# pwm-sg3525a.net
KiCad netlist of a schematic drawn in Altium Designer
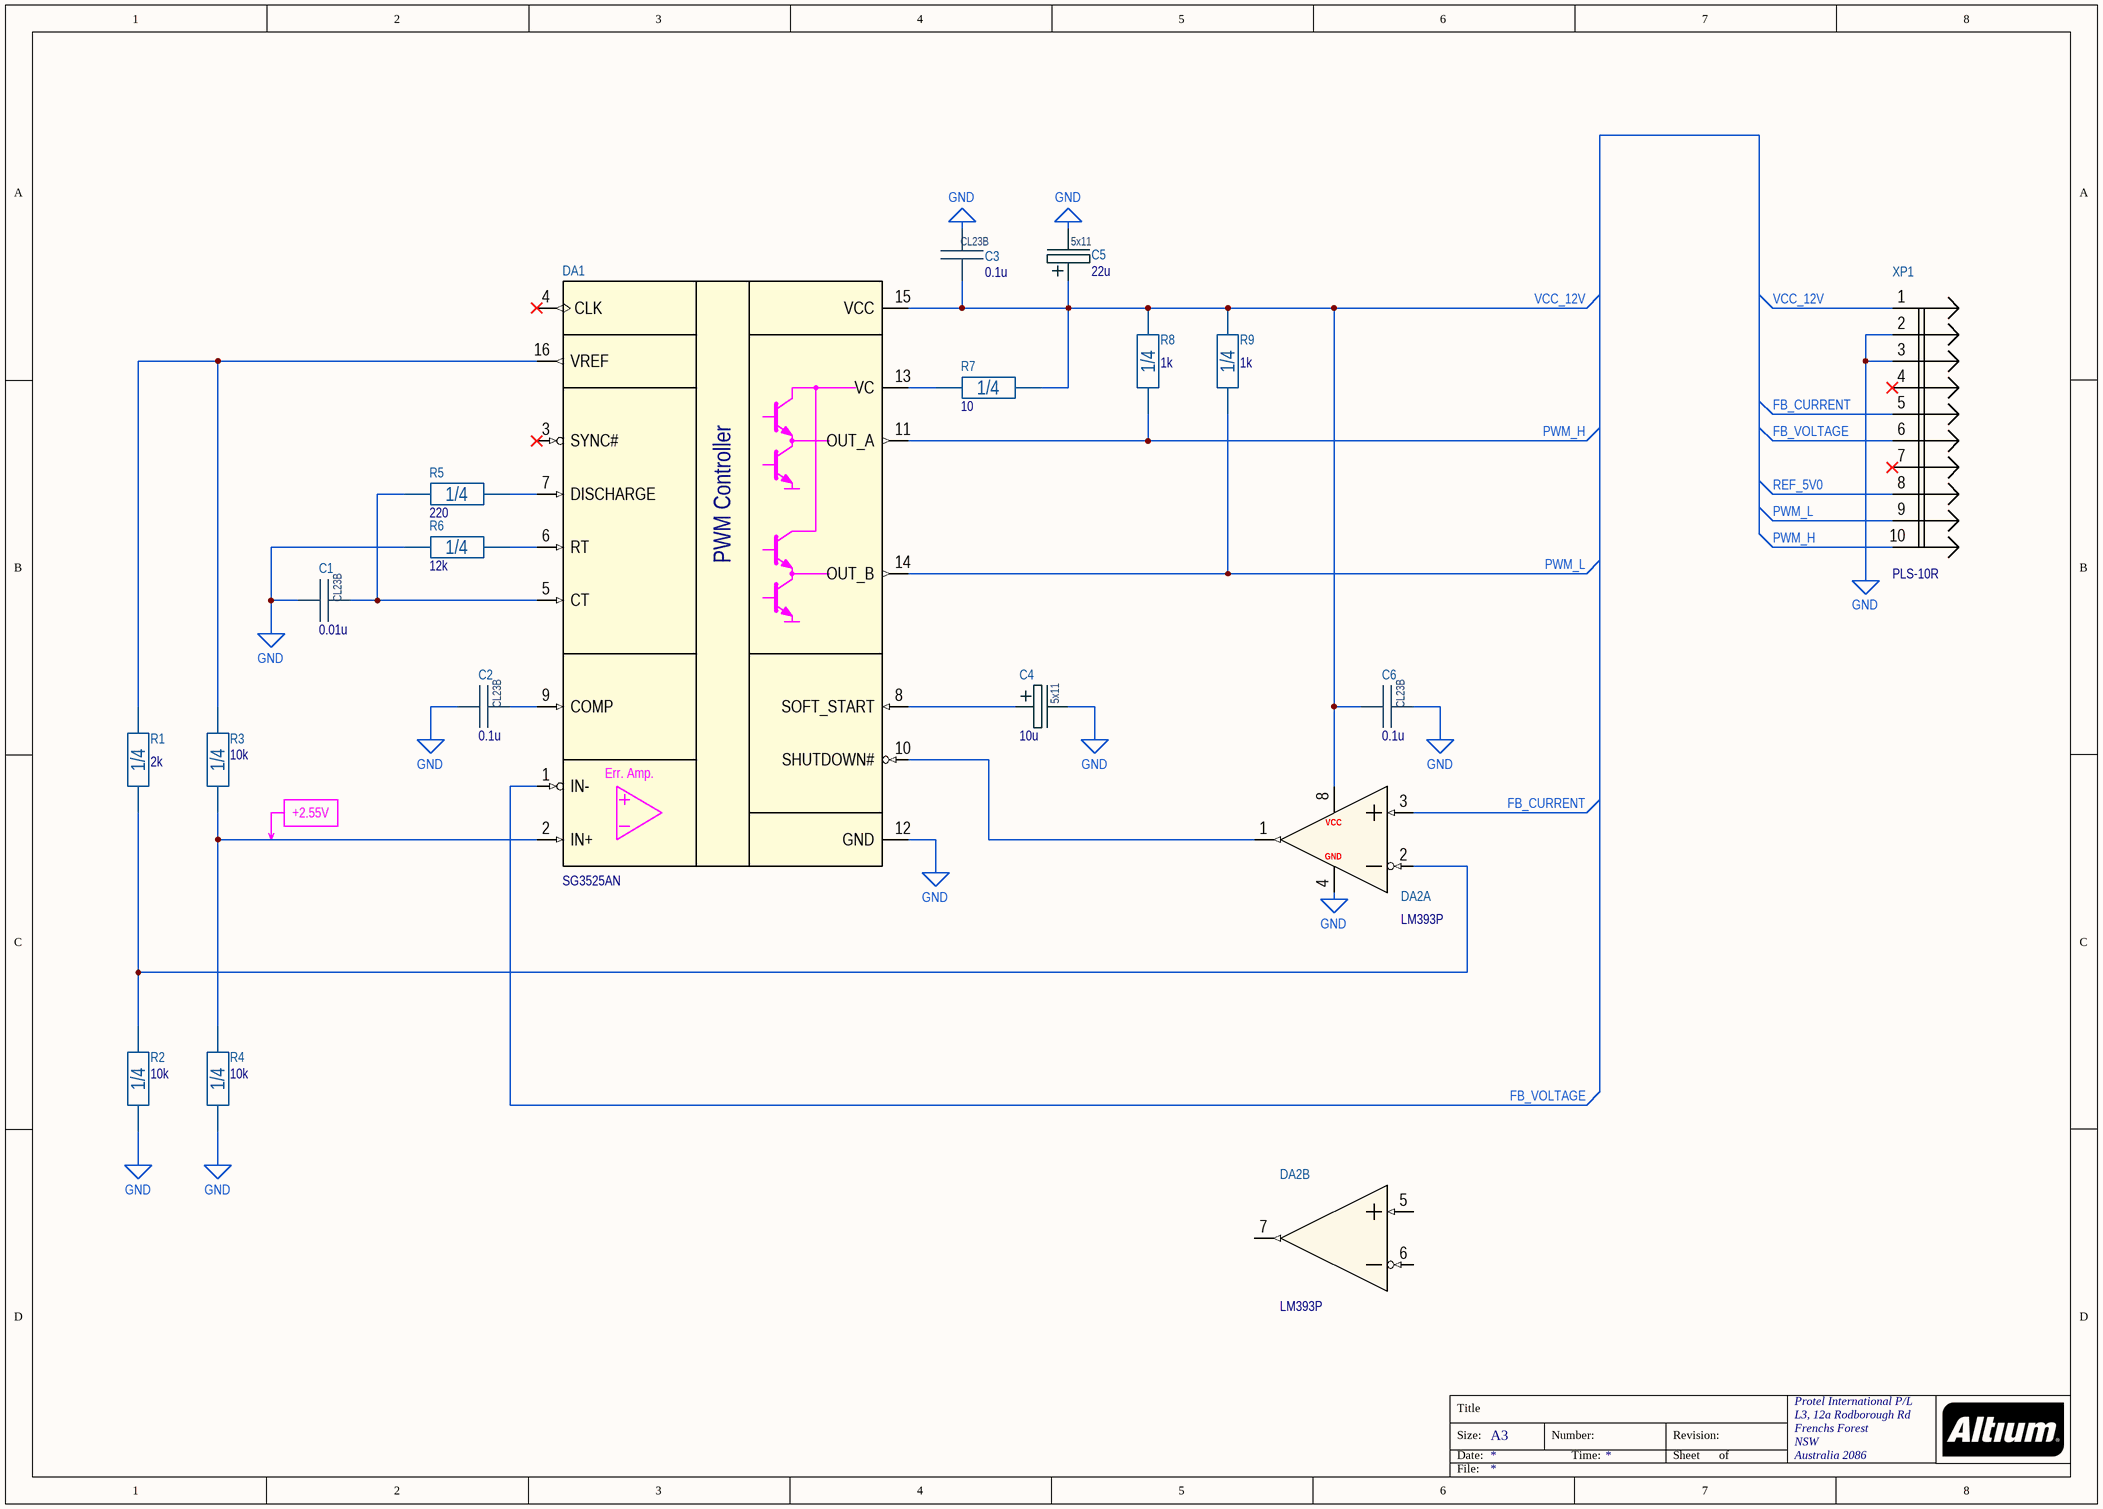
[diagram p0: pwm-sg3525a.SchDoc]

(export (version "E")
  (design (tool "Eeschema 10.0.6"))
  (components
    (comp (ref "C1")
      (value "0.01u")
      (footprint "PcbLib_RC:CL23B_7.2x2.5")
      (description "Box-type metallized polyester film capacitor")
      (fields
        (field (name "TOLERANCE") "± * %")
        (field (name "VOLTAGE") "63V")
        (field (name "PACKAGE") "CL23B")
      )
      (libsource (lib "Schlib_RC") (part "CL23B"))
    )
    (comp (ref "C2")
      (value "0.1u")
      (footprint "PcbLib_RC:CL23B_7.2x2.5")
      (description "Box-type metallized polyester film capacitor")
      (fields
        (field (name "TOLERANCE") "± * %")
        (field (name "VOLTAGE") "63V")
        (field (name "PACKAGE") "CL23B")
      )
      (libsource (lib "Schlib_RC") (part "CL23B"))
    )
    (comp (ref "C3")
      (value "0.1u")
      (footprint "PcbLib_RC:CL23B_7.2x2.5")
      (description "Box-type metallized polyester film capacitor")
      (fields
        (field (name "TOLERANCE") "± * %")
        (field (name "VOLTAGE") "63V")
        (field (name "PACKAGE") "CL23B")
      )
      (libsource (lib "Schlib_RC") (part "CL23B"))
    )
    (comp (ref "C4")
      (value "10u")
      (footprint "PcbLib_RC:ECAP5X11X2.0_BRW")
      (description "Aluminium capacitor")
      (fields
        (field (name "TOLERANCE") "± 20 %")
        (field (name "VOLTAGE") "25V")
        (field (name "PACKAGE") "5x11")
      )
      (libsource (lib "Schlib_RC") (part "C_ECAP"))
    )
    (comp (ref "C5")
      (value "22u")
      (footprint "PcbLib_RC:ECAP5X11X2.0_BRW")
      (description "Aluminium capacitor")
      (fields
        (field (name "TOLERANCE") "± 20 %")
        (field (name "VOLTAGE") "63V")
        (field (name "PACKAGE") "5x11")
      )
      (libsource (lib "Schlib_RC") (part "C_ECAP"))
    )
    (comp (ref "C6")
      (value "0.1u")
      (footprint "PcbLib_RC:CL23B_7.2x2.5")
      (description "Box-type metallized polyester film capacitor")
      (fields
        (field (name "TOLERANCE") "± * %")
        (field (name "VOLTAGE") "63V")
        (field (name "PACKAGE") "CL23B")
      )
      (libsource (lib "Schlib_RC") (part "CL23B"))
    )
    (comp (ref "DA1")
      (value "SG3525AN")
      (footprint "PcbLib_ICs:DIP-16P-M03")
      (description "Pulse-Width-Modulation Control Circuits")
      (fields (field (name "MANUFACTURER") "ON Semiconductor"))
      (libsource (lib "Schlib_ONSemiconductor") (part "SG3525AN"))
    )
    (comp (ref "DA2")
      (value "LM393P")
      (footprint "PcbLib_ICs:DIP-8P-M01_with_SO8")
      (description "Dual Comparator")
      (fields (field (name "MANUFACTURER") "Texas Instruments"))
      (libsource (lib "Schlib_Texas_Instruments") (part "LM393P"))
    )
    (comp (ref "R1")
      (value "2k")
      (footprint "PcbLib_RC:CFR-25")
      (description "Resistor 1/4W")
      (fields
        (field (name "TOLERANCE") "± 1 %")
        (field (name "PART NUMBER") "MFR-25FTF52-2K")
        (field (name "PACKAGE") "1/4")
      )
      (libsource (lib "Schlib_RC") (part "CF25"))
    )
    (comp (ref "R2")
      (value "10k")
      (footprint "PcbLib_RC:CFR-25(VERTICAL)")
      (description "Resistor 1/4W")
      (fields
        (field (name "TOLERANCE") "± 1 %")
        (field (name "PART NUMBER") "MFR-25FTF52-10K")
        (field (name "PACKAGE") "1/4")
      )
      (libsource (lib "Schlib_RC") (part "CF25"))
    )
    (comp (ref "R3")
      (value "10k")
      (footprint "PcbLib_RC:CFR-25(VERTICAL)")
      (description "Resistor 1/4W")
      (fields
        (field (name "TOLERANCE") "± 1 %")
        (field (name "PART NUMBER") "MFR-25FTF52-10K")
        (field (name "PACKAGE") "1/4")
      )
      (libsource (lib "Schlib_RC") (part "CF25"))
    )
    (comp (ref "R4")
      (value "10k")
      (footprint "PcbLib_RC:CFR-25(VERTICAL)")
      (description "Resistor 1/4W")
      (fields
        (field (name "TOLERANCE") "± 1 %")
        (field (name "PART NUMBER") "MFR-25FTF52-10K")
        (field (name "PACKAGE") "1/4")
      )
      (libsource (lib "Schlib_RC") (part "CF25"))
    )
    (comp (ref "R5")
      (value "220")
      (footprint "PcbLib_RC:CFR-25(VERTICAL)")
      (description "Resistor 1/4W")
      (fields
        (field (name "TOLERANCE") "± 1 %")
        (field (name "PART NUMBER") "MFR-25FTF52-220R")
        (field (name "PACKAGE") "1/4")
      )
      (libsource (lib "Schlib_RC") (part "CF25"))
    )
    (comp (ref "R6")
      (value "12k")
      (footprint "PcbLib_RC:CFR-25(VERTICAL)")
      (description "Resistor 1/4W")
      (fields
        (field (name "TOLERANCE") "± 1 %")
        (field (name "PART NUMBER") "MFR-25FTF52-12K")
        (field (name "PACKAGE") "1/4")
      )
      (libsource (lib "Schlib_RC") (part "CF25"))
    )
    (comp (ref "R7")
      (value "10")
      (footprint "PcbLib_RC:CFR-25(VERTICAL)")
      (description "Resistor 1/4W")
      (fields
        (field (name "TOLERANCE") "± 1 %")
        (field (name "PART NUMBER") "MFR-25FTF52-10R")
        (field (name "PACKAGE") "1/4")
      )
      (libsource (lib "Schlib_RC") (part "CF25"))
    )
    (comp (ref "R8")
      (value "1k")
      (footprint "PcbLib_RC:CFR-25(VERTICAL)")
      (description "Resistor 1/4W")
      (fields
        (field (name "TOLERANCE") "± 1 %")
        (field (name "PART NUMBER") "MFR-25FTF52-1K")
        (field (name "PACKAGE") "1/4")
      )
      (libsource (lib "Schlib_RC") (part "CF25"))
    )
    (comp (ref "R9")
      (value "1k")
      (footprint "PcbLib_RC:CFR-25(VERTICAL)")
      (description "Resistor 1/4W")
      (fields
        (field (name "TOLERANCE") "± 1 %")
        (field (name "PART NUMBER") "MFR-25FTF52-1K")
        (field (name "PACKAGE") "1/4")
      )
      (libsource (lib "Schlib_RC") (part "CF25"))
    )
    (comp (ref "XP1")
      (value "PLS-10R")
      (footprint "PcbLib_Pin_Headers:PLS-10R")
      (libsource (lib "Schlib_Pin_Headers") (part "PLS-10R"))
    )
  )
  (nets
    (net (code "1") (name "/FB_CURRENT") (class "Default")
      (node (ref "DA2") (pin "3") (pinfunction "1IN+_3") (pintype "input"))
      (node (ref "XP1") (pin "5") (pinfunction "5_5") (pintype "passive"))
    )
    (net (code "2") (name "/FB_VOLTAGE") (class "Default")
      (node (ref "DA1") (pin "1") (pinfunction "IN-_1") (pintype "input"))
      (node (ref "XP1") (pin "6") (pinfunction "6_6") (pintype "passive"))
    )
    (net (code "3") (name "/PWM_H") (class "Default")
      (node (ref "DA1") (pin "11") (pinfunction "OUT_A_11") (pintype "output"))
      (node (ref "R8") (pin "2") (pinfunction "2_2") (pintype "passive"))
      (node (ref "XP1") (pin "10") (pinfunction "10_10") (pintype "passive"))
    )
    (net (code "4") (name "/PWM_L") (class "Default")
      (node (ref "DA1") (pin "14") (pinfunction "OUT_B_14") (pintype "output"))
      (node (ref "R9") (pin "2") (pinfunction "2_2") (pintype "passive"))
      (node (ref "XP1") (pin "9") (pinfunction "9_9") (pintype "passive"))
    )
    (net (code "5") (name "/REF_5V0") (class "Default")
      (node (ref "XP1") (pin "8") (pinfunction "8_8") (pintype "passive"))
    )
    (net (code "6") (name "/VCC_12V") (class "Default")
      (node (ref "C3") (pin "2") (pinfunction "2_2") (pintype "passive"))
      (node (ref "C5") (pin "1") (pinfunction "1_1") (pintype "passive"))
      (node (ref "C6") (pin "1") (pinfunction "1_1") (pintype "passive"))
      (node (ref "DA1") (pin "15") (pinfunction "VCC_15") (pintype "power_in"))
      (node (ref "DA2") (pin "8") (pinfunction "VCC_8") (pintype "power_in"))
      (node (ref "R7") (pin "1") (pinfunction "1_1") (pintype "passive"))
      (node (ref "R8") (pin "1") (pinfunction "1_1") (pintype "passive"))
      (node (ref "R9") (pin "1") (pinfunction "1_1") (pintype "passive"))
      (node (ref "XP1") (pin "1") (pinfunction "1_1") (pintype "passive"))
    )
    (net (code "7") (name "GND") (class "Default")
      (node (ref "C1") (pin "2") (pinfunction "2_2") (pintype "passive"))
      (node (ref "C2") (pin "2") (pinfunction "2_2") (pintype "passive"))
      (node (ref "C3") (pin "1") (pinfunction "1_1") (pintype "passive"))
      (node (ref "C4") (pin "2") (pinfunction "2_2") (pintype "passive"))
      (node (ref "C5") (pin "2") (pinfunction "2_2") (pintype "passive"))
      (node (ref "C6") (pin "2") (pinfunction "2_2") (pintype "passive"))
      (node (ref "DA1") (pin "12") (pinfunction "GND_12") (pintype "power_in"))
      (node (ref "DA2") (pin "4") (pinfunction "GND_4") (pintype "power_in"))
      (node (ref "R2") (pin "1") (pinfunction "1_1") (pintype "passive"))
      (node (ref "R4") (pin "1") (pinfunction "1_1") (pintype "passive"))
      (node (ref "R6") (pin "2") (pinfunction "2_2") (pintype "passive"))
      (node (ref "XP1") (pin "2") (pinfunction "2_2") (pintype "passive"))
      (node (ref "XP1") (pin "3") (pinfunction "3_3") (pintype "passive"))
    )
    (net (code "8") (name "Net-(DA1-COMP)") (class "Default")
      (node (ref "C2") (pin "1") (pinfunction "1_1") (pintype "passive"))
      (node (ref "DA1") (pin "9") (pinfunction "COMP_9") (pintype "input"))
    )
    (net (code "9") (name "Net-(DA1-CT)") (class "Default")
      (node (ref "C1") (pin "1") (pinfunction "1_1") (pintype "passive"))
      (node (ref "DA1") (pin "5") (pinfunction "CT_5") (pintype "input"))
      (node (ref "R5") (pin "2") (pinfunction "2_2") (pintype "passive"))
    )
    (net (code "10") (name "Net-(DA1-DISCHARGE)") (class "Default")
      (node (ref "DA1") (pin "7") (pinfunction "DISCHARGE_7") (pintype "input"))
      (node (ref "R5") (pin "1") (pinfunction "1_1") (pintype "passive"))
    )
    (net (code "11") (name "Net-(DA1-IN+)") (class "Default")
      (node (ref "DA1") (pin "2") (pinfunction "IN+_2") (pintype "input"))
      (node (ref "R3") (pin "1") (pinfunction "1_1") (pintype "passive"))
      (node (ref "R4") (pin "2") (pinfunction "2_2") (pintype "passive"))
    )
    (net (code "12") (name "Net-(DA1-RT)") (class "Default")
      (node (ref "DA1") (pin "6") (pinfunction "RT_6") (pintype "input"))
      (node (ref "R6") (pin "1") (pinfunction "1_1") (pintype "passive"))
    )
    (net (code "13") (name "Net-(DA1-SHUTDOWN#)") (class "Default")
      (node (ref "DA1") (pin "10") (pinfunction "SHUTDOWN#_10") (pintype "input"))
      (node (ref "DA2") (pin "1") (pinfunction "1OUT_1") (pintype "output"))
    )
    (net (code "14") (name "Net-(DA1-SOFT_START)") (class "Default")
      (node (ref "C4") (pin "1") (pinfunction "1_1") (pintype "passive"))
      (node (ref "DA1") (pin "8") (pinfunction "SOFT_START_8") (pintype "input"))
    )
    (net (code "15") (name "Net-(DA1-VC)") (class "Default")
      (node (ref "DA1") (pin "13") (pinfunction "VC_13") (pintype "power_in"))
      (node (ref "R7") (pin "2") (pinfunction "2_2") (pintype "passive"))
    )
    (net (code "16") (name "Net-(DA1-VREF)") (class "Default")
      (node (ref "DA1") (pin "16") (pinfunction "VREF_16") (pintype "output"))
      (node (ref "R1") (pin "1") (pinfunction "1_1") (pintype "passive"))
      (node (ref "R3") (pin "2") (pinfunction "2_2") (pintype "passive"))
    )
    (net (code "17") (name "Net-(DA2A-1IN-)") (class "Default")
      (node (ref "DA2") (pin "2") (pinfunction "1IN-_2") (pintype "input"))
      (node (ref "R1") (pin "2") (pinfunction "2_2") (pintype "passive"))
      (node (ref "R2") (pin "2") (pinfunction "2_2") (pintype "passive"))
    )
    (net (code "18") (name "unconnected-(DA1-CLK-Pad4)") (class "Default")
      (node (ref "DA1") (pin "4") (pinfunction "CLK_4") (pintype "output+no_connect"))
    )
    (net (code "19") (name "unconnected-(DA1-SYNC#-Pad3)") (class "Default")
      (node (ref "DA1") (pin "3") (pinfunction "SYNC#_3") (pintype "input+no_connect"))
    )
    (net (code "20") (name "unconnected-(DA2B-2IN+-Pad5)") (class "Default")
      (node (ref "DA2") (pin "5") (pinfunction "2IN+_5") (pintype "input"))
    )
    (net (code "21") (name "unconnected-(DA2B-2IN--Pad6)") (class "Default")
      (node (ref "DA2") (pin "6") (pinfunction "2IN-_6") (pintype "input"))
    )
    (net (code "22") (name "unconnected-(DA2B-2OUT-Pad7)") (class "Default")
      (node (ref "DA2") (pin "7") (pinfunction "2OUT_7") (pintype "output"))
    )
    (net (code "23") (name "unconnected-(XP1-Pad4)") (class "Default")
      (node (ref "XP1") (pin "4") (pinfunction "4_4") (pintype "passive+no_connect"))
    )
    (net (code "24") (name "unconnected-(XP1-Pad7)") (class "Default")
      (node (ref "XP1") (pin "7") (pinfunction "7_7") (pintype "passive+no_connect"))
    )
  )
)
